# led-sync.net
KiCad netlist of a schematic drawn in EAGLE
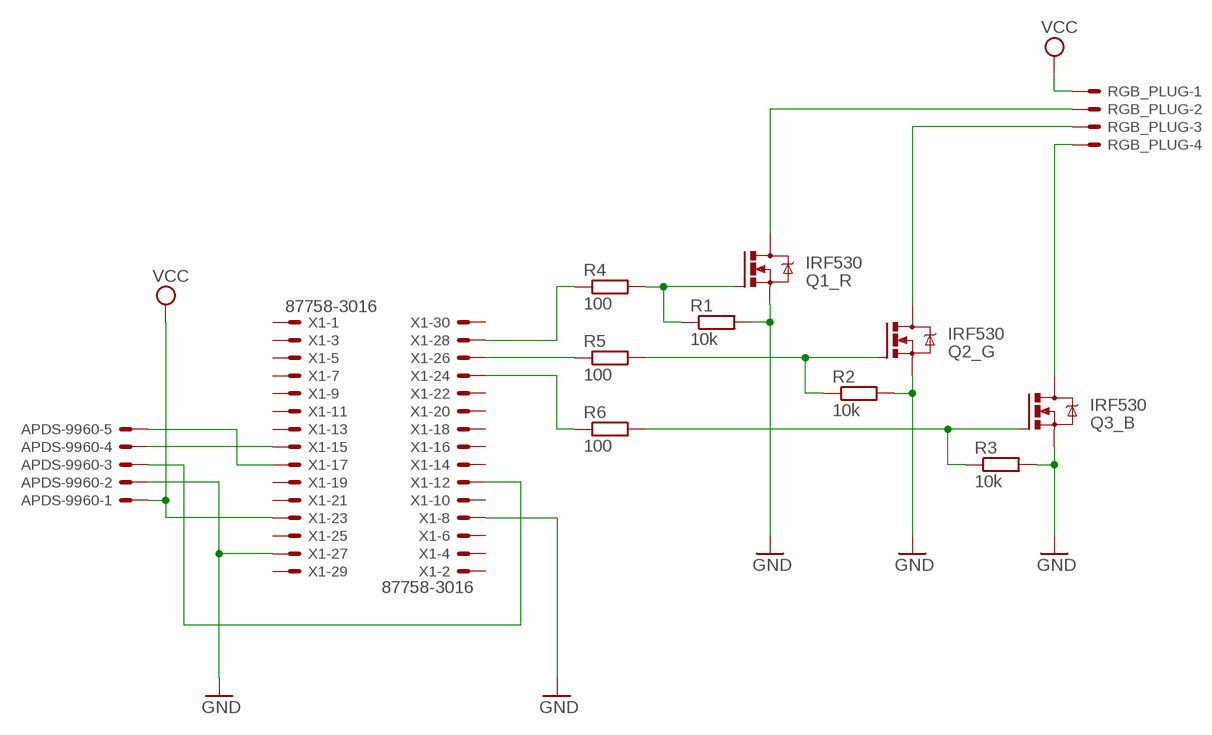
[diagram p0: schematic, sheet 1]

(export (version "E")
  (design (tool "Eeschema 10.0.6"))
  (components
    (comp (ref "APDS-9960")
      (value "22-23-2051")
      (footprint "eagle-import:22-23-2051")
      (fields (field (name "MF") "MOLEX") (field (name "MPN") "APDS-9960"))
      (libsource (lib "eagle-import") (part "22-23-2051"))
    )
    (comp (ref "Q1_R")
      (value "IRF530")
      (footprint "eagle-import:TO220BV")
      (libsource (lib "eagle-import") (part "IRF530"))
    )
    (comp (ref "Q2_G")
      (value "IRF530")
      (footprint "eagle-import:TO220BV")
      (libsource (lib "eagle-import") (part "IRF530"))
    )
    (comp (ref "Q3_B")
      (value "IRF530")
      (footprint "eagle-import:TO220BV")
      (libsource (lib "eagle-import") (part "IRF530"))
    )
    (comp (ref "R1")
      (value "10k")
      (footprint "eagle-import:0207_10")
      (libsource (lib "eagle-import") (part "R-EU_0207/10"))
    )
    (comp (ref "R2")
      (value "10k")
      (footprint "eagle-import:0207_10")
      (libsource (lib "eagle-import") (part "R-EU_0207/10"))
    )
    (comp (ref "R3")
      (value "10k")
      (footprint "eagle-import:0207_10")
      (libsource (lib "eagle-import") (part "R-EU_0207/10"))
    )
    (comp (ref "R4")
      (value "100")
      (footprint "eagle-import:0207_10")
      (libsource (lib "eagle-import") (part "R-EU_0207/10"))
    )
    (comp (ref "R5")
      (value "100")
      (footprint "eagle-import:0207_10")
      (libsource (lib "eagle-import") (part "R-EU_0207/10"))
    )
    (comp (ref "R6")
      (value "100")
      (footprint "eagle-import:0207_10")
      (libsource (lib "eagle-import") (part "R-EU_0207/10"))
    )
    (comp (ref "RGB_PLUG")
      (value "22-23-2041")
      (footprint "eagle-import:22-23-2041")
      (fields (field (name "MF") "MOLEX"))
      (libsource (lib "eagle-import") (part "22-23-2041"))
    )
    (comp (ref "X1")
      (value "87758-3016")
      (footprint "eagle-import:87758-3016")
      (fields (field (name "MF") "MOLEX"))
      (libsource (lib "eagle-import") (part "87758-3016"))
    )
  )
  (nets
    (net (code "1") (name "GND") (class "Default")
      (node (ref "APDS-9960") (pin "2") (pinfunction "S_2") (pintype "passive"))
      (node (ref "Q1_R") (pin "S") (pinfunction "S_S") (pintype "passive"))
      (node (ref "Q2_G") (pin "S") (pinfunction "S_S") (pintype "passive"))
      (node (ref "Q3_B") (pin "S") (pinfunction "S_S") (pintype "passive"))
      (node (ref "R1") (pin "2") (pinfunction "2_2") (pintype "passive"))
      (node (ref "R2") (pin "2") (pinfunction "2_2") (pintype "passive"))
      (node (ref "R3") (pin "2") (pinfunction "2_2") (pintype "passive"))
      (node (ref "X1") (pin "27") (pinfunction "S_27") (pintype "passive"))
      (node (ref "X1") (pin "8") (pinfunction "S_8") (pintype "passive"))
    )
    (net (code "2") (name "Net-(APDS-9960C-S)") (class "Default")
      (node (ref "APDS-9960") (pin "3") (pinfunction "S_3") (pintype "passive"))
      (node (ref "X1") (pin "12") (pinfunction "S_12") (pintype "passive"))
    )
    (net (code "3") (name "Net-(APDS-9960D-S)") (class "Default")
      (node (ref "APDS-9960") (pin "4") (pinfunction "S_4") (pintype "passive"))
      (node (ref "X1") (pin "15") (pinfunction "S_15") (pintype "passive"))
    )
    (net (code "4") (name "Net-(APDS-9960E-S)") (class "Default")
      (node (ref "APDS-9960") (pin "5") (pinfunction "S_5") (pintype "passive"))
      (node (ref "X1") (pin "17") (pinfunction "S_17") (pintype "passive"))
    )
    (net (code "5") (name "Net-(Q1_R-PadG)") (class "Default")
      (node (ref "Q1_R") (pin "G") (pinfunction "G_G") (pintype "passive"))
      (node (ref "R1") (pin "1") (pinfunction "1_1") (pintype "passive"))
      (node (ref "R4") (pin "2") (pinfunction "2_2") (pintype "passive"))
    )
    (net (code "6") (name "Net-(Q2_G-PadG)") (class "Default")
      (node (ref "Q2_G") (pin "G") (pinfunction "G_G") (pintype "passive"))
      (node (ref "R2") (pin "1") (pinfunction "1_1") (pintype "passive"))
      (node (ref "R5") (pin "2") (pinfunction "2_2") (pintype "passive"))
    )
    (net (code "7") (name "Net-(Q3_B-PadG)") (class "Default")
      (node (ref "Q3_B") (pin "G") (pinfunction "G_G") (pintype "passive"))
      (node (ref "R3") (pin "1") (pinfunction "1_1") (pintype "passive"))
      (node (ref "R6") (pin "2") (pinfunction "2_2") (pintype "passive"))
    )
    (net (code "8") (name "Net-(RGB_PLUGB-S)") (class "Default")
      (node (ref "Q1_R") (pin "D") (pinfunction "D_D") (pintype "passive"))
      (node (ref "RGB_PLUG") (pin "2") (pinfunction "S_2") (pintype "passive"))
    )
    (net (code "9") (name "Net-(RGB_PLUGC-S)") (class "Default")
      (node (ref "Q2_G") (pin "D") (pinfunction "D_D") (pintype "passive"))
      (node (ref "RGB_PLUG") (pin "3") (pinfunction "S_3") (pintype "passive"))
    )
    (net (code "10") (name "Net-(RGB_PLUGD-S)") (class "Default")
      (node (ref "Q3_B") (pin "D") (pinfunction "D_D") (pintype "passive"))
      (node (ref "RGB_PLUG") (pin "4") (pinfunction "S_4") (pintype "passive"))
    )
    (net (code "11") (name "Net-(X1Q-S)") (class "Default")
      (node (ref "R6") (pin "1") (pinfunction "1_1") (pintype "passive"))
      (node (ref "X1") (pin "24") (pinfunction "S_24") (pintype "passive"))
    )
    (net (code "12") (name "Net-(X1S-S)") (class "Default")
      (node (ref "R5") (pin "1") (pinfunction "1_1") (pintype "passive"))
      (node (ref "X1") (pin "26") (pinfunction "S_26") (pintype "passive"))
    )
    (net (code "13") (name "Net-(X1U-S)") (class "Default")
      (node (ref "R4") (pin "1") (pinfunction "1_1") (pintype "passive"))
      (node (ref "X1") (pin "28") (pinfunction "S_28") (pintype "passive"))
    )
    (net (code "14") (name "VCC") (class "Default")
      (node (ref "APDS-9960") (pin "1") (pinfunction "S_1") (pintype "passive"))
      (node (ref "RGB_PLUG") (pin "1") (pinfunction "S_1") (pintype "passive"))
      (node (ref "X1") (pin "23") (pinfunction "S_23") (pintype "passive"))
    )
    (net (code "15") (name "unconnected-(X1A-S-Pad1)") (class "Default")
      (node (ref "X1") (pin "1") (pinfunction "S_1") (pintype "passive"))
    )
    (net (code "16") (name "unconnected-(X1AA-S-Pad6)") (class "Default")
      (node (ref "X1") (pin "6") (pinfunction "S_6") (pintype "passive"))
    )
    (net (code "17") (name "unconnected-(X1AB-S-Pad7)") (class "Default")
      (node (ref "X1") (pin "7") (pinfunction "S_7") (pintype "passive"))
    )
    (net (code "18") (name "unconnected-(X1AD-S-Pad9)") (class "Default")
      (node (ref "X1") (pin "9") (pinfunction "S_9") (pintype "passive"))
    )
    (net (code "19") (name "unconnected-(X1B-S-Pad10)") (class "Default")
      (node (ref "X1") (pin "10") (pinfunction "S_10") (pintype "passive"))
    )
    (net (code "20") (name "unconnected-(X1C-S-Pad11)") (class "Default")
      (node (ref "X1") (pin "11") (pinfunction "S_11") (pintype "passive"))
    )
    (net (code "21") (name "unconnected-(X1E-S-Pad13)") (class "Default")
      (node (ref "X1") (pin "13") (pinfunction "S_13") (pintype "passive"))
    )
    (net (code "22") (name "unconnected-(X1F-S-Pad14)") (class "Default")
      (node (ref "X1") (pin "14") (pinfunction "S_14") (pintype "passive"))
    )
    (net (code "23") (name "unconnected-(X1H-S-Pad16)") (class "Default")
      (node (ref "X1") (pin "16") (pinfunction "S_16") (pintype "passive"))
    )
    (net (code "24") (name "unconnected-(X1J-S-Pad18)") (class "Default")
      (node (ref "X1") (pin "18") (pinfunction "S_18") (pintype "passive"))
    )
    (net (code "25") (name "unconnected-(X1K-S-Pad19)") (class "Default")
      (node (ref "X1") (pin "19") (pinfunction "S_19") (pintype "passive"))
    )
    (net (code "26") (name "unconnected-(X1L-S-Pad2)") (class "Default")
      (node (ref "X1") (pin "2") (pinfunction "S_2") (pintype "passive"))
    )
    (net (code "27") (name "unconnected-(X1M-S-Pad20)") (class "Default")
      (node (ref "X1") (pin "20") (pinfunction "S_20") (pintype "passive"))
    )
    (net (code "28") (name "unconnected-(X1N-S-Pad21)") (class "Default")
      (node (ref "X1") (pin "21") (pinfunction "S_21") (pintype "passive"))
    )
    (net (code "29") (name "unconnected-(X1O-S-Pad22)") (class "Default")
      (node (ref "X1") (pin "22") (pinfunction "S_22") (pintype "passive"))
    )
    (net (code "30") (name "unconnected-(X1R-S-Pad25)") (class "Default")
      (node (ref "X1") (pin "25") (pinfunction "S_25") (pintype "passive"))
    )
    (net (code "31") (name "unconnected-(X1V-S-Pad29)") (class "Default")
      (node (ref "X1") (pin "29") (pinfunction "S_29") (pintype "passive"))
    )
    (net (code "32") (name "unconnected-(X1W-S-Pad3)") (class "Default")
      (node (ref "X1") (pin "3") (pinfunction "S_3") (pintype "passive"))
    )
    (net (code "33") (name "unconnected-(X1X-S-Pad30)") (class "Default")
      (node (ref "X1") (pin "30") (pinfunction "S_30") (pintype "passive"))
    )
    (net (code "34") (name "unconnected-(X1Y-S-Pad4)") (class "Default")
      (node (ref "X1") (pin "4") (pinfunction "S_4") (pintype "passive"))
    )
    (net (code "35") (name "unconnected-(X1Z-S-Pad5)") (class "Default")
      (node (ref "X1") (pin "5") (pinfunction "S_5") (pintype "passive"))
    )
  )
)
